# twentyfour.net
KiCad netlist of a schematic drawn in Altium Designer
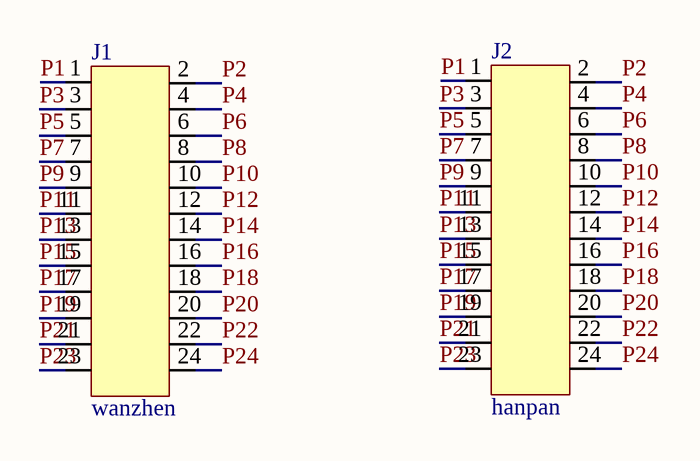
[diagram p0: twentyfour.SchDoc]

(export (version "E")
  (design (tool "Eeschema 10.0.6"))
  (components
    (comp (ref "J1")
      (value "wanzhen")
      (footprint "twentyfour:wanzhen")
      (description "弯针")
      (libsource (lib "twentyfour") (part "wanzhen"))
    )
    (comp (ref "J2")
      (value "hanpan")
      (footprint "twentyfour:hanpan")
      (description "焊盘")
      (libsource (lib "twentyfour") (part "hanpan"))
    )
  )
  (nets
    (net (code "1") (name "/P1") (class "Default")
      (node (ref "J1") (pin "1") (pinfunction "1_1") (pintype "passive"))
      (node (ref "J2") (pin "1") (pinfunction "1_1") (pintype "passive"))
    )
    (net (code "2") (name "/P2") (class "Default")
      (node (ref "J1") (pin "2") (pinfunction "2_2") (pintype "passive"))
      (node (ref "J2") (pin "2") (pinfunction "2_2") (pintype "passive"))
    )
    (net (code "3") (name "/P3") (class "Default")
      (node (ref "J1") (pin "3") (pinfunction "3_3") (pintype "passive"))
      (node (ref "J2") (pin "3") (pinfunction "3_3") (pintype "passive"))
    )
    (net (code "4") (name "/P4") (class "Default")
      (node (ref "J1") (pin "4") (pinfunction "4_4") (pintype "passive"))
      (node (ref "J2") (pin "4") (pinfunction "4_4") (pintype "passive"))
    )
    (net (code "5") (name "/P5") (class "Default")
      (node (ref "J1") (pin "5") (pinfunction "5_5") (pintype "passive"))
      (node (ref "J2") (pin "5") (pinfunction "5_5") (pintype "passive"))
    )
    (net (code "6") (name "/P6") (class "Default")
      (node (ref "J1") (pin "6") (pinfunction "6_6") (pintype "passive"))
      (node (ref "J2") (pin "6") (pinfunction "6_6") (pintype "passive"))
    )
    (net (code "7") (name "/P7") (class "Default")
      (node (ref "J1") (pin "7") (pinfunction "7_7") (pintype "passive"))
      (node (ref "J2") (pin "7") (pinfunction "7_7") (pintype "passive"))
    )
    (net (code "8") (name "/P8") (class "Default")
      (node (ref "J1") (pin "8") (pinfunction "8_8") (pintype "passive"))
      (node (ref "J2") (pin "8") (pinfunction "8_8") (pintype "passive"))
    )
    (net (code "9") (name "/P9") (class "Default")
      (node (ref "J1") (pin "9") (pinfunction "9_9") (pintype "passive"))
      (node (ref "J2") (pin "9") (pinfunction "9_9") (pintype "passive"))
    )
    (net (code "10") (name "/P10") (class "Default")
      (node (ref "J1") (pin "10") (pinfunction "10_10") (pintype "passive"))
      (node (ref "J2") (pin "10") (pinfunction "10_10") (pintype "passive"))
    )
    (net (code "11") (name "/P11") (class "Default")
      (node (ref "J1") (pin "11") (pinfunction "11_11") (pintype "passive"))
      (node (ref "J2") (pin "11") (pinfunction "11_11") (pintype "passive"))
    )
    (net (code "12") (name "/P12") (class "Default")
      (node (ref "J1") (pin "12") (pinfunction "12_12") (pintype "passive"))
      (node (ref "J2") (pin "12") (pinfunction "12_12") (pintype "passive"))
    )
    (net (code "13") (name "/P13") (class "Default")
      (node (ref "J1") (pin "13") (pinfunction "13_13") (pintype "passive"))
      (node (ref "J2") (pin "13") (pinfunction "13_13") (pintype "passive"))
    )
    (net (code "14") (name "/P14") (class "Default")
      (node (ref "J1") (pin "14") (pinfunction "14_14") (pintype "passive"))
      (node (ref "J2") (pin "14") (pinfunction "14_14") (pintype "passive"))
    )
    (net (code "15") (name "/P15") (class "Default")
      (node (ref "J1") (pin "15") (pinfunction "15_15") (pintype "passive"))
      (node (ref "J2") (pin "15") (pinfunction "15_15") (pintype "passive"))
    )
    (net (code "16") (name "/P16") (class "Default")
      (node (ref "J1") (pin "16") (pinfunction "16_16") (pintype "passive"))
      (node (ref "J2") (pin "16") (pinfunction "16_16") (pintype "passive"))
    )
    (net (code "17") (name "/P17") (class "Default")
      (node (ref "J1") (pin "17") (pinfunction "17_17") (pintype "passive"))
      (node (ref "J2") (pin "17") (pinfunction "17_17") (pintype "passive"))
    )
    (net (code "18") (name "/P18") (class "Default")
      (node (ref "J1") (pin "18") (pinfunction "18_18") (pintype "passive"))
      (node (ref "J2") (pin "18") (pinfunction "18_18") (pintype "passive"))
    )
    (net (code "19") (name "/P19") (class "Default")
      (node (ref "J1") (pin "19") (pinfunction "19_19") (pintype "passive"))
      (node (ref "J2") (pin "19") (pinfunction "19_19") (pintype "passive"))
    )
    (net (code "20") (name "/P20") (class "Default")
      (node (ref "J1") (pin "20") (pinfunction "20_20") (pintype "passive"))
      (node (ref "J2") (pin "20") (pinfunction "20_20") (pintype "passive"))
    )
    (net (code "21") (name "/P21") (class "Default")
      (node (ref "J1") (pin "21") (pinfunction "21_21") (pintype "passive"))
      (node (ref "J2") (pin "21") (pinfunction "21_21") (pintype "passive"))
    )
    (net (code "22") (name "/P22") (class "Default")
      (node (ref "J1") (pin "22") (pinfunction "22_22") (pintype "passive"))
      (node (ref "J2") (pin "22") (pinfunction "22_22") (pintype "passive"))
    )
    (net (code "23") (name "/P23") (class "Default")
      (node (ref "J1") (pin "23") (pinfunction "23_23") (pintype "passive"))
      (node (ref "J2") (pin "23") (pinfunction "23_23") (pintype "passive"))
    )
    (net (code "24") (name "/P24") (class "Default")
      (node (ref "J1") (pin "24") (pinfunction "24_24") (pintype "passive"))
      (node (ref "J2") (pin "24") (pinfunction "24_24") (pintype "passive"))
    )
  )
)
